# eightByEight.net
KiCad netlist of a schematic drawn in EAGLE
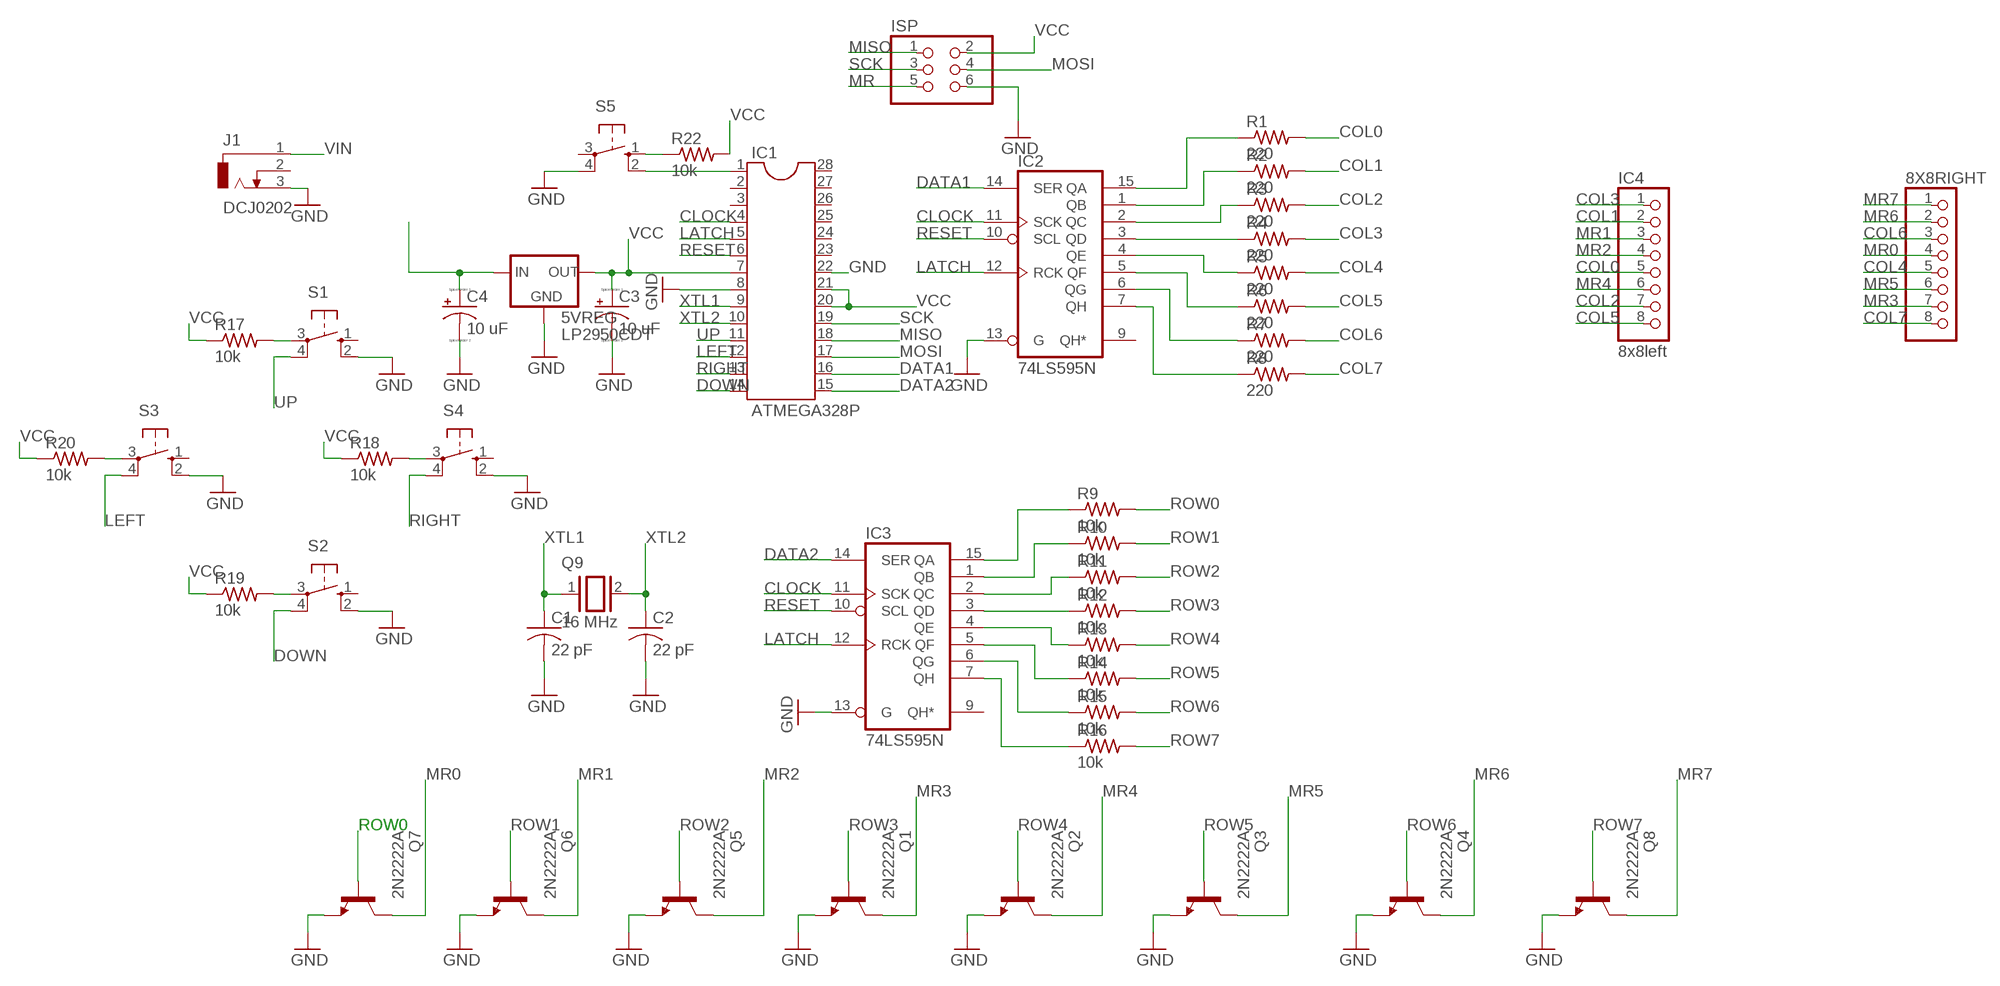
[diagram p0: schematic, sheet 1]

(export (version "E")
  (design (tool "Eeschema 10.0.6"))
  (components
    (comp (ref "5VREG")
      (value "LP2950CDT")
      (footprint "eagle-import:DPACK")
      (libsource (lib "eagle-import") (part "LP2950?CDT-5.0"))
    )
    (comp (ref "8X8RIGHT")
      (value "PINHD-1X8")
      (footprint "eagle-import:1X08")
      (libsource (lib "eagle-import") (part "PINHD-1X8"))
    )
    (comp (ref "C1")
      (value "22 pF")
      (footprint "eagle-import:C0805")
      (libsource (lib "eagle-import") (part "C-USC0805"))
    )
    (comp (ref "C2")
      (value "22 pF")
      (footprint "eagle-import:C0805")
      (libsource (lib "eagle-import") (part "C-USC0805"))
    )
    (comp (ref "C3")
      (value "10 uF")
      (footprint "eagle-import:TT2D5")
      (libsource (lib "eagle-import") (part "CPOL-USTT2D5"))
    )
    (comp (ref "C4")
      (value "10 uF")
      (footprint "eagle-import:TT2D5")
      (libsource (lib "eagle-import") (part "CPOL-USTT2D5"))
    )
    (comp (ref "IC1")
      (value "ATMEGA328P")
      (footprint "eagle-import:DIL28-4")
      (libsource (lib "eagle-import") (part "DIL28-4"))
    )
    (comp (ref "IC2")
      (value "74LS595N")
      (footprint "eagle-import:DIL16")
      (libsource (lib "eagle-import") (part "74595NLS"))
    )
    (comp (ref "IC3")
      (value "74LS595N")
      (footprint "eagle-import:DIL16")
      (libsource (lib "eagle-import") (part "74595NLS"))
    )
    (comp (ref "IC4")
      (value "8x8left")
      (footprint "eagle-import:1X08")
      (libsource (lib "eagle-import") (part "PINHD-1X8"))
    )
    (comp (ref "ISP")
      (value "PINHD-2X3")
      (footprint "eagle-import:2X03")
      (libsource (lib "eagle-import") (part "PINHD-2X3"))
    )
    (comp (ref "J1")
      (value "DCJ0202")
      (footprint "eagle-import:DCJ0202")
      (libsource (lib "eagle-import") (part "DCJ0202"))
    )
    (comp (ref "Q1")
      (value "2N2222A")
      (footprint "eagle-import:TO18")
      (libsource (lib "eagle-import") (part "2N2222A"))
    )
    (comp (ref "Q2")
      (value "2N2222A")
      (footprint "eagle-import:TO18")
      (libsource (lib "eagle-import") (part "2N2222A"))
    )
    (comp (ref "Q3")
      (value "2N2222A")
      (footprint "eagle-import:TO18")
      (libsource (lib "eagle-import") (part "2N2222A"))
    )
    (comp (ref "Q4")
      (value "2N2222A")
      (footprint "eagle-import:TO18")
      (libsource (lib "eagle-import") (part "2N2222A"))
    )
    (comp (ref "Q5")
      (value "2N2222A")
      (footprint "eagle-import:TO18")
      (libsource (lib "eagle-import") (part "2N2222A"))
    )
    (comp (ref "Q6")
      (value "2N2222A")
      (footprint "eagle-import:TO18")
      (libsource (lib "eagle-import") (part "2N2222A"))
    )
    (comp (ref "Q7")
      (value "2N2222A")
      (footprint "eagle-import:TO18")
      (libsource (lib "eagle-import") (part "2N2222A"))
    )
    (comp (ref "Q8")
      (value "2N2222A")
      (footprint "eagle-import:TO18")
      (libsource (lib "eagle-import") (part "2N2222A"))
    )
    (comp (ref "Q9")
      (value "16 MHz")
      (footprint "eagle-import:QS")
      (libsource (lib "eagle-import") (part "XTAL/S"))
    )
    (comp (ref "R1")
      (value "220")
      (footprint "eagle-import:M0805")
      (libsource (lib "eagle-import") (part "R-US_M0805"))
    )
    (comp (ref "R2")
      (value "220")
      (footprint "eagle-import:M0805")
      (libsource (lib "eagle-import") (part "R-US_M0805"))
    )
    (comp (ref "R3")
      (value "220")
      (footprint "eagle-import:M0805")
      (libsource (lib "eagle-import") (part "R-US_M0805"))
    )
    (comp (ref "R4")
      (value "220")
      (footprint "eagle-import:M0805")
      (libsource (lib "eagle-import") (part "R-US_M0805"))
    )
    (comp (ref "R5")
      (value "220")
      (footprint "eagle-import:M0805")
      (libsource (lib "eagle-import") (part "R-US_M0805"))
    )
    (comp (ref "R6")
      (value "220")
      (footprint "eagle-import:M0805")
      (libsource (lib "eagle-import") (part "R-US_M0805"))
    )
    (comp (ref "R7")
      (value "220")
      (footprint "eagle-import:M0805")
      (libsource (lib "eagle-import") (part "R-US_M0805"))
    )
    (comp (ref "R8")
      (value "220")
      (footprint "eagle-import:M0805")
      (libsource (lib "eagle-import") (part "R-US_M0805"))
    )
    (comp (ref "R9")
      (value "10k")
      (footprint "eagle-import:M0805")
      (libsource (lib "eagle-import") (part "R-US_M0805"))
    )
    (comp (ref "R10")
      (value "10k")
      (footprint "eagle-import:M0805")
      (libsource (lib "eagle-import") (part "R-US_M0805"))
    )
    (comp (ref "R11")
      (value "10k")
      (footprint "eagle-import:M0805")
      (libsource (lib "eagle-import") (part "R-US_M0805"))
    )
    (comp (ref "R12")
      (value "10k")
      (footprint "eagle-import:M0805")
      (libsource (lib "eagle-import") (part "R-US_M0805"))
    )
    (comp (ref "R13")
      (value "10k")
      (footprint "eagle-import:M0805")
      (libsource (lib "eagle-import") (part "R-US_M0805"))
    )
    (comp (ref "R14")
      (value "10k")
      (footprint "eagle-import:M0805")
      (libsource (lib "eagle-import") (part "R-US_M0805"))
    )
    (comp (ref "R15")
      (value "10k")
      (footprint "eagle-import:M0805")
      (libsource (lib "eagle-import") (part "R-US_M0805"))
    )
    (comp (ref "R16")
      (value "10k")
      (footprint "eagle-import:M0805")
      (libsource (lib "eagle-import") (part "R-US_M0805"))
    )
    (comp (ref "R17")
      (value "10k")
      (footprint "eagle-import:M0805")
      (libsource (lib "eagle-import") (part "R-US_M0805"))
    )
    (comp (ref "R18")
      (value "10k")
      (footprint "eagle-import:M0805")
      (libsource (lib "eagle-import") (part "R-US_M0805"))
    )
    (comp (ref "R19")
      (value "10k")
      (footprint "eagle-import:M0805")
      (libsource (lib "eagle-import") (part "R-US_M0805"))
    )
    (comp (ref "R20")
      (value "10k")
      (footprint "eagle-import:M0805")
      (libsource (lib "eagle-import") (part "R-US_M0805"))
    )
    (comp (ref "R22")
      (value "10k")
      (footprint "eagle-import:M0805")
      (libsource (lib "eagle-import") (part "R-US_M0805"))
    )
    (comp (ref "S1")
      (value "10-XX")
      (footprint "eagle-import:B3F-10XX")
      (fields (field (name "MPN") "B3F-1000"))
      (libsource (lib "eagle-import") (part "10-XX"))
    )
    (comp (ref "S2")
      (value "10-XX")
      (footprint "eagle-import:B3F-10XX")
      (fields (field (name "MPN") "B3F-1000"))
      (libsource (lib "eagle-import") (part "10-XX"))
    )
    (comp (ref "S3")
      (value "10-XX")
      (footprint "eagle-import:B3F-10XX")
      (fields (field (name "MPN") "B3F-1000"))
      (libsource (lib "eagle-import") (part "10-XX"))
    )
    (comp (ref "S4")
      (value "10-XX")
      (footprint "eagle-import:B3F-10XX")
      (fields (field (name "MPN") "B3F-1000"))
      (libsource (lib "eagle-import") (part "10-XX"))
    )
    (comp (ref "S5")
      (value "10-XX")
      (footprint "eagle-import:B3F-10XX")
      (fields (field (name "MPN") "B3F-1000"))
      (libsource (lib "eagle-import") (part "10-XX"))
    )
  )
  (nets
    (net (code "1") (name "/CLOCK") (class "Default")
      (node (ref "IC1") (pin "4") (pinfunction "4_4") (pintype "passive"))
      (node (ref "IC2") (pin "11") (pinfunction "SCK_11") (pintype "input"))
      (node (ref "IC3") (pin "11") (pinfunction "SCK_11") (pintype "input"))
    )
    (net (code "2") (name "/COL0") (class "Default")
      (node (ref "IC4") (pin "5") (pinfunction "5_5") (pintype "passive"))
      (node (ref "R1") (pin "2") (pinfunction "2_2") (pintype "passive"))
    )
    (net (code "3") (name "/COL1") (class "Default")
      (node (ref "IC4") (pin "2") (pinfunction "2_2") (pintype "passive"))
      (node (ref "R2") (pin "2") (pinfunction "2_2") (pintype "passive"))
    )
    (net (code "4") (name "/COL2") (class "Default")
      (node (ref "IC4") (pin "7") (pinfunction "7_7") (pintype "passive"))
      (node (ref "R3") (pin "2") (pinfunction "2_2") (pintype "passive"))
    )
    (net (code "5") (name "/COL3") (class "Default")
      (node (ref "IC4") (pin "1") (pinfunction "1_1") (pintype "passive"))
      (node (ref "R4") (pin "2") (pinfunction "2_2") (pintype "passive"))
    )
    (net (code "6") (name "/COL4") (class "Default")
      (node (ref "8X8RIGHT") (pin "5") (pinfunction "5_5") (pintype "passive"))
      (node (ref "R5") (pin "2") (pinfunction "2_2") (pintype "passive"))
    )
    (net (code "7") (name "/COL5") (class "Default")
      (node (ref "IC4") (pin "8") (pinfunction "8_8") (pintype "passive"))
      (node (ref "R6") (pin "2") (pinfunction "2_2") (pintype "passive"))
    )
    (net (code "8") (name "/COL6") (class "Default")
      (node (ref "8X8RIGHT") (pin "3") (pinfunction "3_3") (pintype "passive"))
      (node (ref "R7") (pin "2") (pinfunction "2_2") (pintype "passive"))
    )
    (net (code "9") (name "/COL7") (class "Default")
      (node (ref "8X8RIGHT") (pin "8") (pinfunction "8_8") (pintype "passive"))
      (node (ref "R8") (pin "2") (pinfunction "2_2") (pintype "passive"))
    )
    (net (code "10") (name "/DATA1") (class "Default")
      (node (ref "IC1") (pin "16") (pinfunction "16_16") (pintype "passive"))
      (node (ref "IC2") (pin "14") (pinfunction "SER_14") (pintype "input"))
    )
    (net (code "11") (name "/DATA2") (class "Default")
      (node (ref "IC1") (pin "15") (pinfunction "15_15") (pintype "passive"))
      (node (ref "IC3") (pin "14") (pinfunction "SER_14") (pintype "input"))
    )
    (net (code "12") (name "/DOWN") (class "Default")
      (node (ref "IC1") (pin "14") (pinfunction "14_14") (pintype "passive"))
      (node (ref "S2") (pin "4") (pinfunction "P1_4") (pintype "passive"))
    )
    (net (code "13") (name "/LATCH") (class "Default")
      (node (ref "IC1") (pin "5") (pinfunction "5_5") (pintype "passive"))
      (node (ref "IC2") (pin "12") (pinfunction "RCK_12") (pintype "input"))
      (node (ref "IC3") (pin "12") (pinfunction "RCK_12") (pintype "input"))
    )
    (net (code "14") (name "/LEFT") (class "Default")
      (node (ref "IC1") (pin "12") (pinfunction "12_12") (pintype "passive"))
      (node (ref "S3") (pin "4") (pinfunction "P1_4") (pintype "passive"))
    )
    (net (code "15") (name "/MISO") (class "Default")
      (node (ref "IC1") (pin "18") (pinfunction "18_18") (pintype "passive"))
      (node (ref "ISP") (pin "1") (pinfunction "1_1") (pintype "passive"))
    )
    (net (code "16") (name "/MOSI") (class "Default")
      (node (ref "IC1") (pin "17") (pinfunction "17_17") (pintype "passive"))
      (node (ref "ISP") (pin "4") (pinfunction "4_4") (pintype "passive"))
    )
    (net (code "17") (name "/MR") (class "Default")
      (node (ref "IC1") (pin "1") (pinfunction "1_1") (pintype "passive"))
      (node (ref "ISP") (pin "5") (pinfunction "5_5") (pintype "passive"))
      (node (ref "S5") (pin "2") (pinfunction "S1_2") (pintype "passive"))
    )
    (net (code "18") (name "/MR0") (class "Default")
      (node (ref "8X8RIGHT") (pin "4") (pinfunction "4_4") (pintype "passive"))
      (node (ref "Q7") (pin "3") (pinfunction "C_3") (pintype "passive"))
    )
    (net (code "19") (name "/MR1") (class "Default")
      (node (ref "IC4") (pin "3") (pinfunction "3_3") (pintype "passive"))
      (node (ref "Q6") (pin "3") (pinfunction "C_3") (pintype "passive"))
    )
    (net (code "20") (name "/MR2") (class "Default")
      (node (ref "IC4") (pin "4") (pinfunction "4_4") (pintype "passive"))
      (node (ref "Q5") (pin "3") (pinfunction "C_3") (pintype "passive"))
    )
    (net (code "21") (name "/MR3") (class "Default")
      (node (ref "8X8RIGHT") (pin "7") (pinfunction "7_7") (pintype "passive"))
      (node (ref "Q1") (pin "3") (pinfunction "C_3") (pintype "passive"))
    )
    (net (code "22") (name "/MR4") (class "Default")
      (node (ref "IC4") (pin "6") (pinfunction "6_6") (pintype "passive"))
      (node (ref "Q2") (pin "3") (pinfunction "C_3") (pintype "passive"))
    )
    (net (code "23") (name "/MR5") (class "Default")
      (node (ref "8X8RIGHT") (pin "6") (pinfunction "6_6") (pintype "passive"))
      (node (ref "Q3") (pin "3") (pinfunction "C_3") (pintype "passive"))
    )
    (net (code "24") (name "/MR6") (class "Default")
      (node (ref "8X8RIGHT") (pin "2") (pinfunction "2_2") (pintype "passive"))
      (node (ref "Q4") (pin "3") (pinfunction "C_3") (pintype "passive"))
    )
    (net (code "25") (name "/MR7") (class "Default")
      (node (ref "8X8RIGHT") (pin "1") (pinfunction "1_1") (pintype "passive"))
      (node (ref "Q8") (pin "3") (pinfunction "C_3") (pintype "passive"))
    )
    (net (code "26") (name "/RESET") (class "Default")
      (node (ref "IC1") (pin "6") (pinfunction "6_6") (pintype "passive"))
      (node (ref "IC2") (pin "10") (pinfunction "SCL_10") (pintype "input"))
      (node (ref "IC3") (pin "10") (pinfunction "SCL_10") (pintype "input"))
    )
    (net (code "27") (name "/RIGHT") (class "Default")
      (node (ref "IC1") (pin "13") (pinfunction "13_13") (pintype "passive"))
      (node (ref "S4") (pin "4") (pinfunction "P1_4") (pintype "passive"))
    )
    (net (code "28") (name "/ROW0") (class "Default")
      (node (ref "Q7") (pin "2") (pinfunction "B_2") (pintype "passive"))
      (node (ref "R9") (pin "2") (pinfunction "2_2") (pintype "passive"))
    )
    (net (code "29") (name "/ROW1") (class "Default")
      (node (ref "Q6") (pin "2") (pinfunction "B_2") (pintype "passive"))
      (node (ref "R10") (pin "2") (pinfunction "2_2") (pintype "passive"))
    )
    (net (code "30") (name "/ROW2") (class "Default")
      (node (ref "Q5") (pin "2") (pinfunction "B_2") (pintype "passive"))
      (node (ref "R11") (pin "2") (pinfunction "2_2") (pintype "passive"))
    )
    (net (code "31") (name "/ROW3") (class "Default")
      (node (ref "Q1") (pin "2") (pinfunction "B_2") (pintype "passive"))
      (node (ref "R12") (pin "2") (pinfunction "2_2") (pintype "passive"))
    )
    (net (code "32") (name "/ROW4") (class "Default")
      (node (ref "Q2") (pin "2") (pinfunction "B_2") (pintype "passive"))
      (node (ref "R13") (pin "2") (pinfunction "2_2") (pintype "passive"))
    )
    (net (code "33") (name "/ROW5") (class "Default")
      (node (ref "Q3") (pin "2") (pinfunction "B_2") (pintype "passive"))
      (node (ref "R14") (pin "2") (pinfunction "2_2") (pintype "passive"))
    )
    (net (code "34") (name "/ROW6") (class "Default")
      (node (ref "Q4") (pin "2") (pinfunction "B_2") (pintype "passive"))
      (node (ref "R15") (pin "2") (pinfunction "2_2") (pintype "passive"))
    )
    (net (code "35") (name "/ROW7") (class "Default")
      (node (ref "Q8") (pin "2") (pinfunction "B_2") (pintype "passive"))
      (node (ref "R16") (pin "2") (pinfunction "2_2") (pintype "passive"))
    )
    (net (code "36") (name "/SCK") (class "Default")
      (node (ref "IC1") (pin "19") (pinfunction "19_19") (pintype "passive"))
      (node (ref "ISP") (pin "3") (pinfunction "3_3") (pintype "passive"))
    )
    (net (code "37") (name "/UP") (class "Default")
      (node (ref "IC1") (pin "11") (pinfunction "11_11") (pintype "passive"))
      (node (ref "S1") (pin "4") (pinfunction "P1_4") (pintype "passive"))
    )
    (net (code "38") (name "/VCC") (class "Default")
      (node (ref "5VREG") (pin "3") (pinfunction "OUT_3") (pintype "passive"))
      (node (ref "C3") (pin "+") (pinfunction "+_+") (pintype "passive"))
      (node (ref "IC1") (pin "20") (pinfunction "20_20") (pintype "passive"))
      (node (ref "IC1") (pin "21") (pinfunction "21_21") (pintype "passive"))
      (node (ref "IC1") (pin "7") (pinfunction "7_7") (pintype "passive"))
      (node (ref "ISP") (pin "2") (pinfunction "2_2") (pintype "passive"))
      (node (ref "R17") (pin "1") (pinfunction "1_1") (pintype "passive"))
      (node (ref "R18") (pin "1") (pinfunction "1_1") (pintype "passive"))
      (node (ref "R19") (pin "1") (pinfunction "1_1") (pintype "passive"))
      (node (ref "R20") (pin "1") (pinfunction "1_1") (pintype "passive"))
      (node (ref "R22") (pin "2") (pinfunction "2_2") (pintype "passive"))
    )
    (net (code "39") (name "/VIN") (class "Default")
      (node (ref "5VREG") (pin "1") (pinfunction "IN_1") (pintype "input"))
      (node (ref "C4") (pin "+") (pinfunction "+_+") (pintype "passive"))
      (node (ref "J1") (pin "1") (pinfunction "1_1") (pintype "passive"))
    )
    (net (code "40") (name "/XTL1") (class "Default")
      (node (ref "C1") (pin "1") (pinfunction "1_1") (pintype "passive"))
      (node (ref "IC1") (pin "9") (pinfunction "9_9") (pintype "passive"))
      (node (ref "Q9") (pin "1") (pinfunction "1_1") (pintype "passive"))
    )
    (net (code "41") (name "/XTL2") (class "Default")
      (node (ref "C2") (pin "1") (pinfunction "1_1") (pintype "passive"))
      (node (ref "IC1") (pin "10") (pinfunction "10_10") (pintype "passive"))
      (node (ref "Q9") (pin "2") (pinfunction "2_2") (pintype "passive"))
    )
    (net (code "42") (name "GND") (class "Default")
      (node (ref "5VREG") (pin "4") (pinfunction "GND_4") (pintype "input"))
      (node (ref "C1") (pin "2") (pinfunction "2_2") (pintype "passive"))
      (node (ref "C2") (pin "2") (pinfunction "2_2") (pintype "passive"))
      (node (ref "C3") (pin "-") (pinfunction "-_-") (pintype "passive"))
      (node (ref "C4") (pin "-") (pinfunction "-_-") (pintype "passive"))
      (node (ref "IC1") (pin "22") (pinfunction "22_22") (pintype "passive"))
      (node (ref "IC1") (pin "8") (pinfunction "8_8") (pintype "passive"))
      (node (ref "IC2") (pin "13") (pinfunction "G_13") (pintype "input"))
      (node (ref "IC3") (pin "13") (pinfunction "G_13") (pintype "input"))
      (node (ref "ISP") (pin "6") (pinfunction "6_6") (pintype "passive"))
      (node (ref "J1") (pin "3") (pinfunction "3_3") (pintype "passive"))
      (node (ref "Q1") (pin "1") (pinfunction "E_1") (pintype "passive"))
      (node (ref "Q2") (pin "1") (pinfunction "E_1") (pintype "passive"))
      (node (ref "Q3") (pin "1") (pinfunction "E_1") (pintype "passive"))
      (node (ref "Q4") (pin "1") (pinfunction "E_1") (pintype "passive"))
      (node (ref "Q5") (pin "1") (pinfunction "E_1") (pintype "passive"))
      (node (ref "Q6") (pin "1") (pinfunction "E_1") (pintype "passive"))
      (node (ref "Q7") (pin "1") (pinfunction "E_1") (pintype "passive"))
      (node (ref "Q8") (pin "1") (pinfunction "E_1") (pintype "passive"))
      (node (ref "S1") (pin "2") (pinfunction "S1_2") (pintype "passive"))
      (node (ref "S2") (pin "2") (pinfunction "S1_2") (pintype "passive"))
      (node (ref "S3") (pin "2") (pinfunction "S1_2") (pintype "passive"))
      (node (ref "S4") (pin "2") (pinfunction "S1_2") (pintype "passive"))
      (node (ref "S5") (pin "4") (pinfunction "P1_4") (pintype "passive"))
    )
    (net (code "43") (name "Net-(IC2A-QA)") (class "Default")
      (node (ref "IC2") (pin "15") (pinfunction "QA_15") (pintype "tri_state"))
      (node (ref "R1") (pin "1") (pinfunction "1_1") (pintype "passive"))
    )
    (net (code "44") (name "Net-(IC2A-QB)") (class "Default")
      (node (ref "IC2") (pin "1") (pinfunction "QB_1") (pintype "tri_state"))
      (node (ref "R2") (pin "1") (pinfunction "1_1") (pintype "passive"))
    )
    (net (code "45") (name "Net-(IC2A-QC)") (class "Default")
      (node (ref "IC2") (pin "2") (pinfunction "QC_2") (pintype "tri_state"))
      (node (ref "R3") (pin "1") (pinfunction "1_1") (pintype "passive"))
    )
    (net (code "46") (name "Net-(IC2A-QD)") (class "Default")
      (node (ref "IC2") (pin "3") (pinfunction "QD_3") (pintype "tri_state"))
      (node (ref "R4") (pin "1") (pinfunction "1_1") (pintype "passive"))
    )
    (net (code "47") (name "Net-(IC2A-QE)") (class "Default")
      (node (ref "IC2") (pin "4") (pinfunction "QE_4") (pintype "tri_state"))
      (node (ref "R5") (pin "1") (pinfunction "1_1") (pintype "passive"))
    )
    (net (code "48") (name "Net-(IC2A-QF)") (class "Default")
      (node (ref "IC2") (pin "5") (pinfunction "QF_5") (pintype "tri_state"))
      (node (ref "R6") (pin "1") (pinfunction "1_1") (pintype "passive"))
    )
    (net (code "49") (name "Net-(IC2A-QG)") (class "Default")
      (node (ref "IC2") (pin "6") (pinfunction "QG_6") (pintype "tri_state"))
      (node (ref "R7") (pin "1") (pinfunction "1_1") (pintype "passive"))
    )
    (net (code "50") (name "Net-(IC2A-QH)") (class "Default")
      (node (ref "IC2") (pin "7") (pinfunction "QH_7") (pintype "tri_state"))
      (node (ref "R8") (pin "1") (pinfunction "1_1") (pintype "passive"))
    )
    (net (code "51") (name "Net-(IC3A-QA)") (class "Default")
      (node (ref "IC3") (pin "15") (pinfunction "QA_15") (pintype "tri_state"))
      (node (ref "R9") (pin "1") (pinfunction "1_1") (pintype "passive"))
    )
    (net (code "52") (name "Net-(IC3A-QB)") (class "Default")
      (node (ref "IC3") (pin "1") (pinfunction "QB_1") (pintype "tri_state"))
      (node (ref "R10") (pin "1") (pinfunction "1_1") (pintype "passive"))
    )
    (net (code "53") (name "Net-(IC3A-QC)") (class "Default")
      (node (ref "IC3") (pin "2") (pinfunction "QC_2") (pintype "tri_state"))
      (node (ref "R11") (pin "1") (pinfunction "1_1") (pintype "passive"))
    )
    (net (code "54") (name "Net-(IC3A-QD)") (class "Default")
      (node (ref "IC3") (pin "3") (pinfunction "QD_3") (pintype "tri_state"))
      (node (ref "R12") (pin "1") (pinfunction "1_1") (pintype "passive"))
    )
    (net (code "55") (name "Net-(IC3A-QE)") (class "Default")
      (node (ref "IC3") (pin "4") (pinfunction "QE_4") (pintype "tri_state"))
      (node (ref "R13") (pin "1") (pinfunction "1_1") (pintype "passive"))
    )
    (net (code "56") (name "Net-(IC3A-QF)") (class "Default")
      (node (ref "IC3") (pin "5") (pinfunction "QF_5") (pintype "tri_state"))
      (node (ref "R14") (pin "1") (pinfunction "1_1") (pintype "passive"))
    )
    (net (code "57") (name "Net-(IC3A-QG)") (class "Default")
      (node (ref "IC3") (pin "6") (pinfunction "QG_6") (pintype "tri_state"))
      (node (ref "R15") (pin "1") (pinfunction "1_1") (pintype "passive"))
    )
    (net (code "58") (name "Net-(IC3A-QH)") (class "Default")
      (node (ref "IC3") (pin "7") (pinfunction "QH_7") (pintype "tri_state"))
      (node (ref "R16") (pin "1") (pinfunction "1_1") (pintype "passive"))
    )
    (net (code "59") (name "Net-(S1-P)") (class "Default")
      (node (ref "R17") (pin "2") (pinfunction "2_2") (pintype "passive"))
      (node (ref "S1") (pin "3") (pinfunction "P_3") (pintype "passive"))
    )
    (net (code "60") (name "Net-(S2-P)") (class "Default")
      (node (ref "R19") (pin "2") (pinfunction "2_2") (pintype "passive"))
      (node (ref "S2") (pin "3") (pinfunction "P_3") (pintype "passive"))
    )
    (net (code "61") (name "Net-(S3-P)") (class "Default")
      (node (ref "R20") (pin "2") (pinfunction "2_2") (pintype "passive"))
      (node (ref "S3") (pin "3") (pinfunction "P_3") (pintype "passive"))
    )
    (net (code "62") (name "Net-(S4-P)") (class "Default")
      (node (ref "R18") (pin "2") (pinfunction "2_2") (pintype "passive"))
      (node (ref "S4") (pin "3") (pinfunction "P_3") (pintype "passive"))
    )
    (net (code "63") (name "Net-(S5-S)") (class "Default")
      (node (ref "R22") (pin "1") (pinfunction "1_1") (pintype "passive"))
      (node (ref "S5") (pin "1") (pinfunction "S_1") (pintype "passive"))
    )
    (net (code "64") (name "unconnected-(IC1-Pad2)") (class "Default")
      (node (ref "IC1") (pin "2") (pinfunction "2_2") (pintype "passive"))
    )
    (net (code "65") (name "unconnected-(IC1-Pad3)") (class "Default")
      (node (ref "IC1") (pin "3") (pinfunction "3_3") (pintype "passive"))
    )
    (net (code "66") (name "unconnected-(IC1-Pad23)") (class "Default")
      (node (ref "IC1") (pin "23") (pinfunction "23_23") (pintype "passive"))
    )
    (net (code "67") (name "unconnected-(IC1-Pad24)") (class "Default")
      (node (ref "IC1") (pin "24") (pinfunction "24_24") (pintype "passive"))
    )
    (net (code "68") (name "unconnected-(IC1-Pad25)") (class "Default")
      (node (ref "IC1") (pin "25") (pinfunction "25_25") (pintype "passive"))
    )
    (net (code "69") (name "unconnected-(IC1-Pad26)") (class "Default")
      (node (ref "IC1") (pin "26") (pinfunction "26_26") (pintype "passive"))
    )
    (net (code "70") (name "unconnected-(IC1-Pad27)") (class "Default")
      (node (ref "IC1") (pin "27") (pinfunction "27_27") (pintype "passive"))
    )
    (net (code "71") (name "unconnected-(IC1-Pad28)") (class "Default")
      (node (ref "IC1") (pin "28") (pinfunction "28_28") (pintype "passive"))
    )
    (net (code "72") (name "unconnected-(IC2A-QH*-Pad9)") (class "Default")
      (node (ref "IC2") (pin "9") (pinfunction "QH*_9") (pintype "tri_state"))
    )
    (net (code "73") (name "unconnected-(IC3A-QH*-Pad9)") (class "Default")
      (node (ref "IC3") (pin "9") (pinfunction "QH*_9") (pintype "tri_state"))
    )
    (net (code "74") (name "unconnected-(J1-Pad2)") (class "Default")
      (node (ref "J1") (pin "2") (pinfunction "2_2") (pintype "passive"))
    )
    (net (code "75") (name "unconnected-(S1-S-Pad1)") (class "Default")
      (node (ref "S1") (pin "1") (pinfunction "S_1") (pintype "passive"))
    )
    (net (code "76") (name "unconnected-(S2-S-Pad1)") (class "Default")
      (node (ref "S2") (pin "1") (pinfunction "S_1") (pintype "passive"))
    )
    (net (code "77") (name "unconnected-(S3-S-Pad1)") (class "Default")
      (node (ref "S3") (pin "1") (pinfunction "S_1") (pintype "passive"))
    )
    (net (code "78") (name "unconnected-(S4-S-Pad1)") (class "Default")
      (node (ref "S4") (pin "1") (pinfunction "S_1") (pintype "passive"))
    )
    (net (code "79") (name "unconnected-(S5-P-Pad3)") (class "Default")
      (node (ref "S5") (pin "3") (pinfunction "P_3") (pintype "passive"))
    )
  )
)
